# LIC_V-00237-00.net
KiCad netlist of a schematic drawn in EAGLE
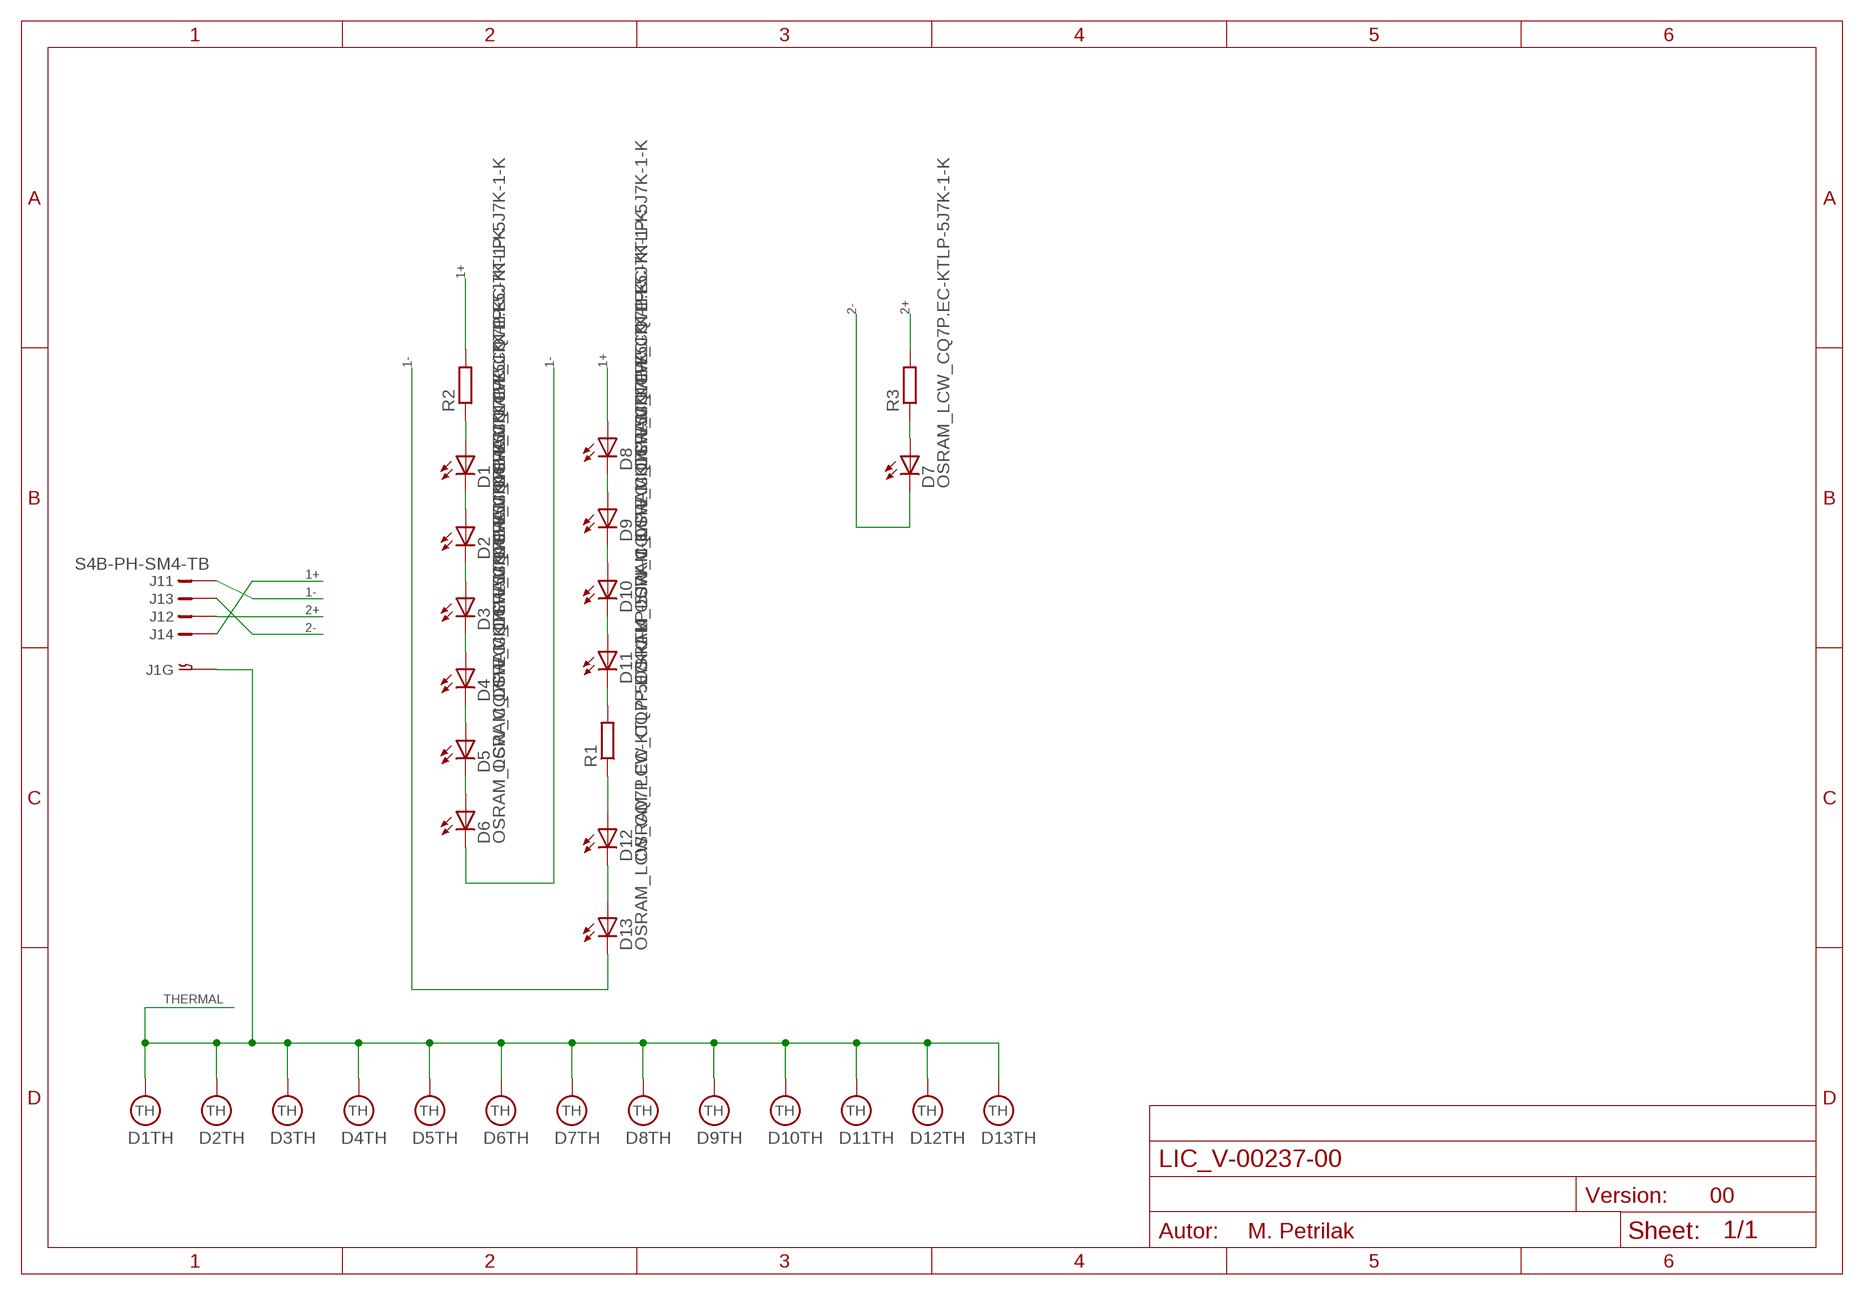
[diagram p0: schematic, sheet 1]

(export (version "E")
  (design (tool "Eeschema 10.0.6"))
  (components
    (comp (ref "D1")
      (value "OSRAM_LCW_CQ7P.EC-KTLP-5J7K-1-K")
      (footprint "eagle-import:OSRAM_LCW")
      (libsource (lib "eagle-import") (part "OSRAM_LCW_CQ7P.EC-KTLP-5J7K-1-K"))
    )
    (comp (ref "D2")
      (value "OSRAM_LCW_CQ7P.EC-KTLP-5J7K-1-K")
      (footprint "eagle-import:OSRAM_LCW")
      (libsource (lib "eagle-import") (part "OSRAM_LCW_CQ7P.EC-KTLP-5J7K-1-K"))
    )
    (comp (ref "D3")
      (value "OSRAM_LCW_CQ7P.EC-KTLP-5J7K-1-K")
      (footprint "eagle-import:OSRAM_LCW")
      (libsource (lib "eagle-import") (part "OSRAM_LCW_CQ7P.EC-KTLP-5J7K-1-K"))
    )
    (comp (ref "D4")
      (value "OSRAM_LCW_CQ7P.EC-KTLP-5J7K-1-K")
      (footprint "eagle-import:OSRAM_LCW")
      (libsource (lib "eagle-import") (part "OSRAM_LCW_CQ7P.EC-KTLP-5J7K-1-K"))
    )
    (comp (ref "D5")
      (value "OSRAM_LCW_CQ7P.EC-KTLP-5J7K-1-K")
      (footprint "eagle-import:OSRAM_LCW")
      (libsource (lib "eagle-import") (part "OSRAM_LCW_CQ7P.EC-KTLP-5J7K-1-K"))
    )
    (comp (ref "D6")
      (value "OSRAM_LCW_CQ7P.EC-KTLP-5J7K-1-K")
      (footprint "eagle-import:OSRAM_LCW")
      (libsource (lib "eagle-import") (part "OSRAM_LCW_CQ7P.EC-KTLP-5J7K-1-K"))
    )
    (comp (ref "D7")
      (value "OSRAM_LCW_CQ7P.EC-KTLP-5J7K-1-K")
      (footprint "eagle-import:OSRAM_LCW")
      (libsource (lib "eagle-import") (part "OSRAM_LCW_CQ7P.EC-KTLP-5J7K-1-K"))
    )
    (comp (ref "D8")
      (value "OSRAM_LCW_CQ7P.EC-KTLP-5J7K-1-K")
      (footprint "eagle-import:OSRAM_LCW")
      (libsource (lib "eagle-import") (part "OSRAM_LCW_CQ7P.EC-KTLP-5J7K-1-K"))
    )
    (comp (ref "D9")
      (value "OSRAM_LCW_CQ7P.EC-KTLP-5J7K-1-K")
      (footprint "eagle-import:OSRAM_LCW")
      (libsource (lib "eagle-import") (part "OSRAM_LCW_CQ7P.EC-KTLP-5J7K-1-K"))
    )
    (comp (ref "D10")
      (value "OSRAM_LCW_CQ7P.EC-KTLP-5J7K-1-K")
      (footprint "eagle-import:OSRAM_LCW")
      (libsource (lib "eagle-import") (part "OSRAM_LCW_CQ7P.EC-KTLP-5J7K-1-K"))
    )
    (comp (ref "D11")
      (value "OSRAM_LCW_CQ7P.EC-KTLP-5J7K-1-K")
      (footprint "eagle-import:OSRAM_LCW")
      (libsource (lib "eagle-import") (part "OSRAM_LCW_CQ7P.EC-KTLP-5J7K-1-K"))
    )
    (comp (ref "D12")
      (value "OSRAM_LCW_CQ7P.EC-KTLP-5J7K-1-K")
      (footprint "eagle-import:OSRAM_LCW")
      (libsource (lib "eagle-import") (part "OSRAM_LCW_CQ7P.EC-KTLP-5J7K-1-K"))
    )
    (comp (ref "D13")
      (value "OSRAM_LCW_CQ7P.EC-KTLP-5J7K-1-K")
      (footprint "eagle-import:OSRAM_LCW")
      (libsource (lib "eagle-import") (part "OSRAM_LCW_CQ7P.EC-KTLP-5J7K-1-K"))
    )
    (comp (ref "J1")
      (value "S4B-PH-SM4-TB")
      (footprint "eagle-import:S4B-PH-SM4-TB")
      (libsource (lib "eagle-import") (part "?4B-PH-SM4-TBS"))
    )
    (comp (ref "R1")
      (value "R-EU_R1206")
      (footprint "eagle-import:R1206")
      (libsource (lib "eagle-import") (part "R-EU_R1206"))
    )
    (comp (ref "R2")
      (value "R-EU_R1206")
      (footprint "eagle-import:R1206")
      (libsource (lib "eagle-import") (part "R-EU_R1206"))
    )
    (comp (ref "R3")
      (value "R-EU_R1206")
      (footprint "eagle-import:R1206")
      (libsource (lib "eagle-import") (part "R-EU_R1206"))
    )
  )
  (nets
    (net (code "1") (name "/1+") (class "Default")
      (node (ref "D8") (pin "A") (pinfunction "A_A") (pintype "passive"))
      (node (ref "J1") (pin "4") (pinfunction "1_4") (pintype "passive"))
      (node (ref "R2") (pin "2") (pinfunction "2_2") (pintype "passive"))
    )
    (net (code "2") (name "/1-") (class "Default")
      (node (ref "D13") (pin "C") (pinfunction "C_C") (pintype "passive"))
      (node (ref "D6") (pin "C") (pinfunction "C_C") (pintype "passive"))
      (node (ref "J1") (pin "1") (pinfunction "1_1") (pintype "passive"))
    )
    (net (code "3") (name "/2+") (class "Default")
      (node (ref "J1") (pin "2") (pinfunction "1_2") (pintype "passive"))
      (node (ref "R3") (pin "2") (pinfunction "2_2") (pintype "passive"))
    )
    (net (code "4") (name "/2-") (class "Default")
      (node (ref "D7") (pin "C") (pinfunction "C_C") (pintype "passive"))
      (node (ref "J1") (pin "3") (pinfunction "1_3") (pintype "passive"))
    )
    (net (code "5") (name "/THERMAL") (class "Default")
      (node (ref "D1") (pin "THERMAL") (pinfunction "TH_THERMAL") (pintype "passive"))
      (node (ref "D10") (pin "THERMAL") (pinfunction "TH_THERMAL") (pintype "passive"))
      (node (ref "D11") (pin "THERMAL") (pinfunction "TH_THERMAL") (pintype "passive"))
      (node (ref "D12") (pin "THERMAL") (pinfunction "TH_THERMAL") (pintype "passive"))
      (node (ref "D13") (pin "THERMAL") (pinfunction "TH_THERMAL") (pintype "passive"))
      (node (ref "D2") (pin "THERMAL") (pinfunction "TH_THERMAL") (pintype "passive"))
      (node (ref "D3") (pin "THERMAL") (pinfunction "TH_THERMAL") (pintype "passive"))
      (node (ref "D4") (pin "THERMAL") (pinfunction "TH_THERMAL") (pintype "passive"))
      (node (ref "D5") (pin "THERMAL") (pinfunction "TH_THERMAL") (pintype "passive"))
      (node (ref "D6") (pin "THERMAL") (pinfunction "TH_THERMAL") (pintype "passive"))
      (node (ref "D7") (pin "THERMAL") (pinfunction "TH_THERMAL") (pintype "passive"))
      (node (ref "D8") (pin "THERMAL") (pinfunction "TH_THERMAL") (pintype "passive"))
      (node (ref "D9") (pin "THERMAL") (pinfunction "TH_THERMAL") (pintype "passive"))
      (node (ref "J1") (pin "GND1") (pinfunction "1_GND1") (pintype "passive"))
      (node (ref "J1") (pin "GND2") (pinfunction "1_GND2") (pintype "passive"))
    )
    (net (code "6") (name "Net-(D1-PadA)") (class "Default")
      (node (ref "D1") (pin "A") (pinfunction "A_A") (pintype "passive"))
      (node (ref "R2") (pin "1") (pinfunction "1_1") (pintype "passive"))
    )
    (net (code "7") (name "Net-(D1-PadC)") (class "Default")
      (node (ref "D1") (pin "C") (pinfunction "C_C") (pintype "passive"))
      (node (ref "D2") (pin "A") (pinfunction "A_A") (pintype "passive"))
    )
    (net (code "8") (name "Net-(D2-PadC)") (class "Default")
      (node (ref "D2") (pin "C") (pinfunction "C_C") (pintype "passive"))
      (node (ref "D3") (pin "A") (pinfunction "A_A") (pintype "passive"))
    )
    (net (code "9") (name "Net-(D3-PadC)") (class "Default")
      (node (ref "D3") (pin "C") (pinfunction "C_C") (pintype "passive"))
      (node (ref "D4") (pin "A") (pinfunction "A_A") (pintype "passive"))
    )
    (net (code "10") (name "Net-(D4-PadC)") (class "Default")
      (node (ref "D4") (pin "C") (pinfunction "C_C") (pintype "passive"))
      (node (ref "D5") (pin "A") (pinfunction "A_A") (pintype "passive"))
    )
    (net (code "11") (name "Net-(D5-PadC)") (class "Default")
      (node (ref "D5") (pin "C") (pinfunction "C_C") (pintype "passive"))
      (node (ref "D6") (pin "A") (pinfunction "A_A") (pintype "passive"))
    )
    (net (code "12") (name "Net-(D7-PadA)") (class "Default")
      (node (ref "D7") (pin "A") (pinfunction "A_A") (pintype "passive"))
      (node (ref "R3") (pin "1") (pinfunction "1_1") (pintype "passive"))
    )
    (net (code "13") (name "Net-(D8-PadC)") (class "Default")
      (node (ref "D8") (pin "C") (pinfunction "C_C") (pintype "passive"))
      (node (ref "D9") (pin "A") (pinfunction "A_A") (pintype "passive"))
    )
    (net (code "14") (name "Net-(D10-PadA)") (class "Default")
      (node (ref "D10") (pin "A") (pinfunction "A_A") (pintype "passive"))
      (node (ref "D9") (pin "C") (pinfunction "C_C") (pintype "passive"))
    )
    (net (code "15") (name "Net-(D10-PadC)") (class "Default")
      (node (ref "D10") (pin "C") (pinfunction "C_C") (pintype "passive"))
      (node (ref "D11") (pin "A") (pinfunction "A_A") (pintype "passive"))
    )
    (net (code "16") (name "Net-(D11-PadC)") (class "Default")
      (node (ref "D11") (pin "C") (pinfunction "C_C") (pintype "passive"))
      (node (ref "R1") (pin "2") (pinfunction "2_2") (pintype "passive"))
    )
    (net (code "17") (name "Net-(D12-PadA)") (class "Default")
      (node (ref "D12") (pin "A") (pinfunction "A_A") (pintype "passive"))
      (node (ref "R1") (pin "1") (pinfunction "1_1") (pintype "passive"))
    )
    (net (code "18") (name "Net-(D12-PadC)") (class "Default")
      (node (ref "D12") (pin "C") (pinfunction "C_C") (pintype "passive"))
      (node (ref "D13") (pin "A") (pinfunction "A_A") (pintype "passive"))
    )
  )
)
